# Arduino_Mega_Breakout_-_Schematic.net
KiCad netlist of a schematic drawn in EAGLE
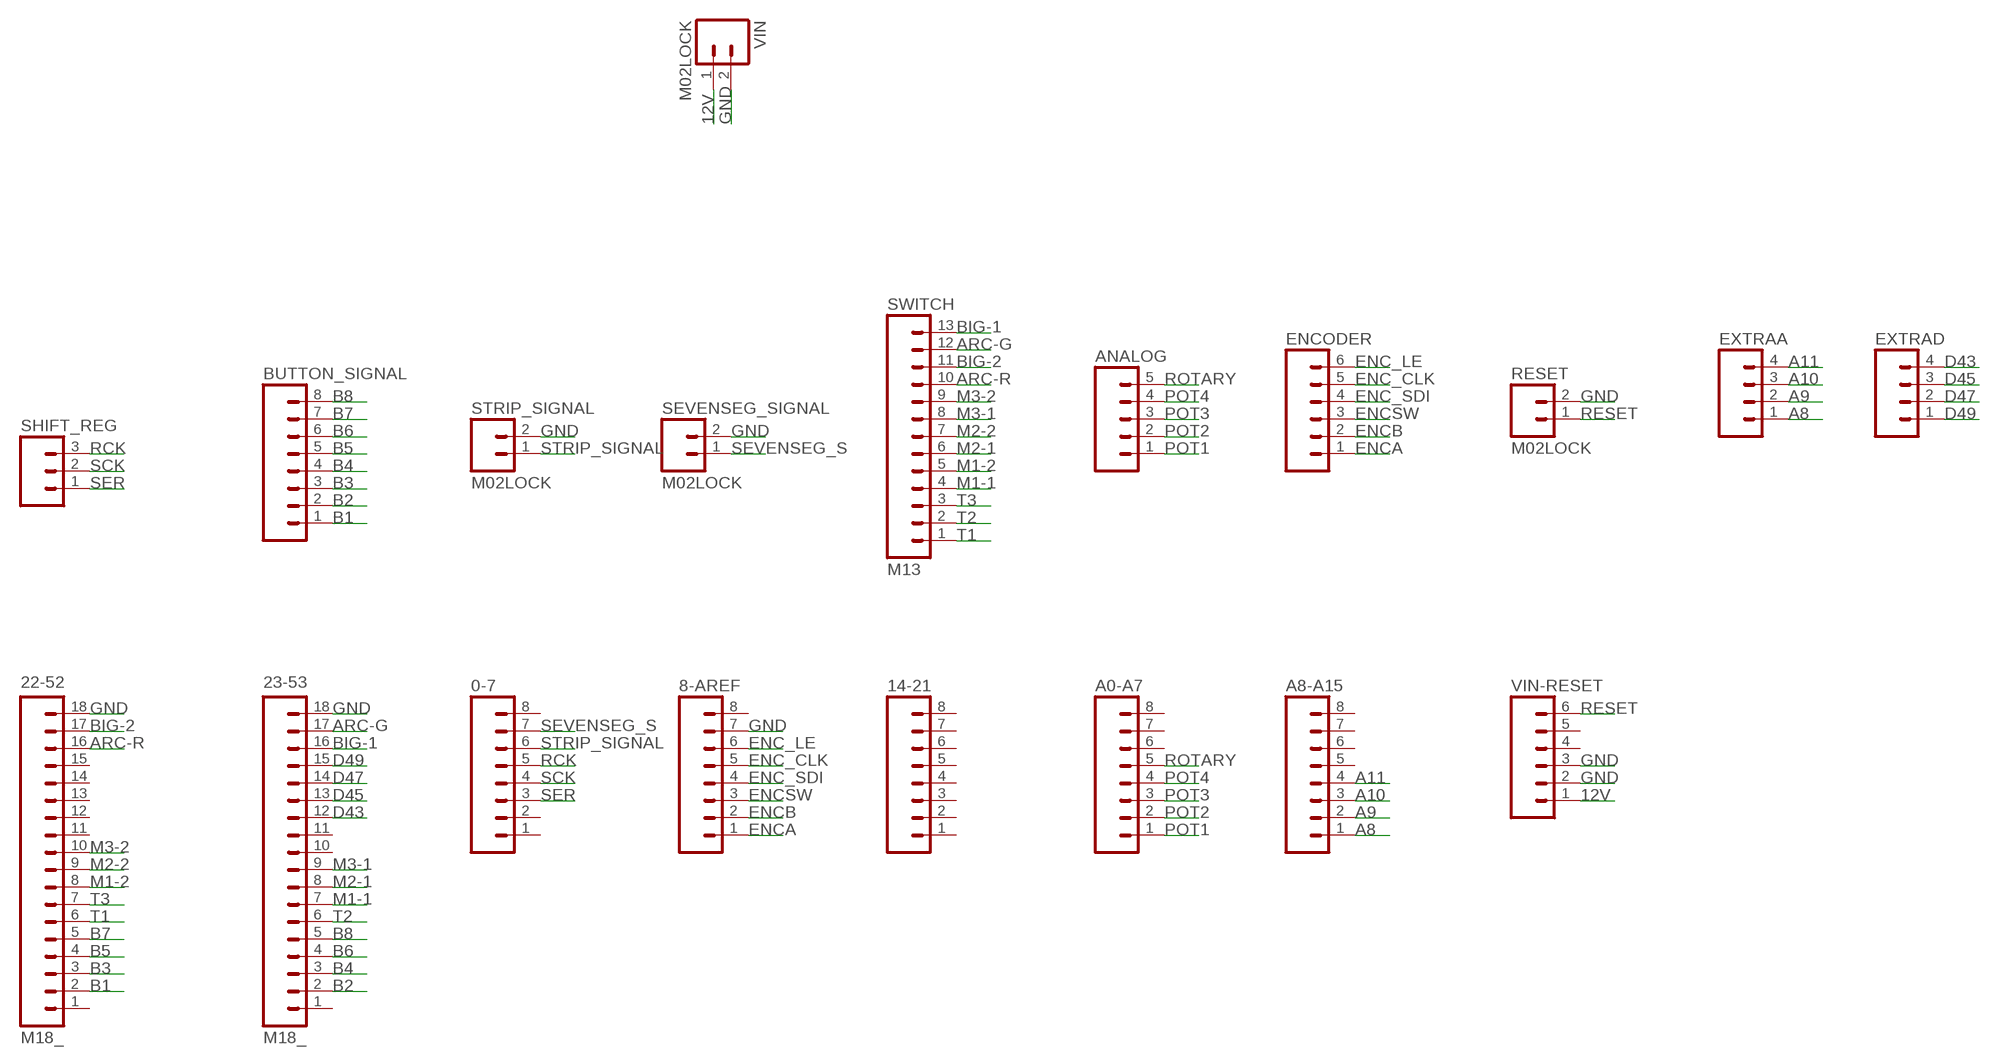
[diagram p0: schematic, sheet 1]

(export (version "E")
  (design (tool "Eeschema 10.0.6"))
  (components
    (comp (ref "0-7")
      (value "M08LOCK")
      (footprint "eagle-import:1X08_LOCK")
      (libsource (lib "eagle-import") (part "M08LOCK"))
    )
    (comp (ref "8-AREF")
      (value "M08LOCK")
      (footprint "eagle-import:1X08_LOCK")
      (libsource (lib "eagle-import") (part "M08LOCK"))
    )
    (comp (ref "14-21")
      (value "M08LOCK")
      (footprint "eagle-import:1X08_LOCK")
      (libsource (lib "eagle-import") (part "M08LOCK"))
    )
    (comp (ref "22-52")
      (value "M18_")
      (footprint "eagle-import:1X18")
      (libsource (lib "eagle-import") (part "M18_"))
    )
    (comp (ref "23-53")
      (value "M18_")
      (footprint "eagle-import:1X18")
      (libsource (lib "eagle-import") (part "M18_"))
    )
    (comp (ref "A0-A7")
      (value "M08LOCK")
      (footprint "eagle-import:1X08_LOCK")
      (libsource (lib "eagle-import") (part "M08LOCK"))
    )
    (comp (ref "A8-A15")
      (value "M08LOCK")
      (footprint "eagle-import:1X08_LOCK")
      (libsource (lib "eagle-import") (part "M08LOCK"))
    )
    (comp (ref "ANALOG")
      (value "M05LOCK")
      (footprint "eagle-import:1X05_LOCK")
      (libsource (lib "eagle-import") (part "M05LOCK"))
    )
    (comp (ref "BUTTON_SIGNAL")
      (value "M08")
      (footprint "eagle-import:1X08_PIN1_NO_SILK")
      (libsource (lib "eagle-import") (part "M08"))
    )
    (comp (ref "ENCODER")
      (value "M06LOCK")
      (footprint "eagle-import:1X06_LOCK")
      (libsource (lib "eagle-import") (part "M06LOCK"))
    )
    (comp (ref "EXTRAA")
      (value "M04LOCK")
      (footprint "eagle-import:1X04_LOCK")
      (libsource (lib "eagle-import") (part "M04LOCK"))
    )
    (comp (ref "EXTRAD")
      (value "M04PTH")
      (footprint "eagle-import:1X04")
      (libsource (lib "eagle-import") (part "M04PTH"))
    )
    (comp (ref "RESET")
      (value "M02LOCK")
      (footprint "eagle-import:1X02_LOCK")
      (libsource (lib "eagle-import") (part "M02LOCK"))
    )
    (comp (ref "SEVENSEG_SIGNAL")
      (value "M02LOCK")
      (footprint "eagle-import:1X02_LOCK")
      (libsource (lib "eagle-import") (part "M02LOCK"))
    )
    (comp (ref "SHIFT_REG")
      (value "M03LOCK")
      (footprint "eagle-import:1X03_LOCK")
      (libsource (lib "eagle-import") (part "M03LOCK"))
    )
    (comp (ref "STRIP_SIGNAL")
      (value "M02LOCK")
      (footprint "eagle-import:1X02_LOCK")
      (libsource (lib "eagle-import") (part "M02LOCK"))
    )
    (comp (ref "SWITCH")
      (value "M13")
      (footprint "eagle-import:1X13")
      (libsource (lib "eagle-import") (part "M13"))
    )
    (comp (ref "VIN")
      (value "M02LOCK")
      (footprint "eagle-import:1X02_LOCK")
      (libsource (lib "eagle-import") (part "M02LOCK"))
    )
    (comp (ref "VIN-RESET")
      (value "M06LOCK")
      (footprint "eagle-import:1X06_LOCK")
      (libsource (lib "eagle-import") (part "M06LOCK"))
    )
  )
  (nets
    (net (code "1") (name "/12V") (class "Default")
      (node (ref "VIN") (pin "1") (pinfunction "1_1") (pintype "passive"))
      (node (ref "VIN-RESET") (pin "1") (pinfunction "1_1") (pintype "passive"))
    )
    (net (code "2") (name "/A8") (class "Default")
      (node (ref "A8-A15") (pin "1") (pinfunction "1_1") (pintype "passive"))
      (node (ref "EXTRAA") (pin "1") (pinfunction "1_1") (pintype "passive"))
    )
    (net (code "3") (name "/A9") (class "Default")
      (node (ref "A8-A15") (pin "2") (pinfunction "2_2") (pintype "passive"))
      (node (ref "EXTRAA") (pin "2") (pinfunction "2_2") (pintype "passive"))
    )
    (net (code "4") (name "/A10") (class "Default")
      (node (ref "A8-A15") (pin "3") (pinfunction "3_3") (pintype "passive"))
      (node (ref "EXTRAA") (pin "3") (pinfunction "3_3") (pintype "passive"))
    )
    (net (code "5") (name "/A11") (class "Default")
      (node (ref "A8-A15") (pin "4") (pinfunction "4_4") (pintype "passive"))
      (node (ref "EXTRAA") (pin "4") (pinfunction "4_4") (pintype "passive"))
    )
    (net (code "6") (name "/ARC-G") (class "Default")
      (node (ref "23-53") (pin "17") (pinfunction "17_17") (pintype "passive"))
      (node (ref "SWITCH") (pin "12") (pinfunction "12_12") (pintype "passive"))
    )
    (net (code "7") (name "/ARC-R") (class "Default")
      (node (ref "22-52") (pin "16") (pinfunction "16_16") (pintype "passive"))
      (node (ref "SWITCH") (pin "10") (pinfunction "10_10") (pintype "passive"))
    )
    (net (code "8") (name "/B1") (class "Default")
      (node (ref "22-52") (pin "2") (pinfunction "2_2") (pintype "passive"))
      (node (ref "BUTTON_SIGNAL") (pin "1") (pinfunction "1_1") (pintype "passive"))
    )
    (net (code "9") (name "/B2") (class "Default")
      (node (ref "23-53") (pin "2") (pinfunction "2_2") (pintype "passive"))
      (node (ref "BUTTON_SIGNAL") (pin "2") (pinfunction "2_2") (pintype "passive"))
    )
    (net (code "10") (name "/B3") (class "Default")
      (node (ref "22-52") (pin "3") (pinfunction "3_3") (pintype "passive"))
      (node (ref "BUTTON_SIGNAL") (pin "3") (pinfunction "3_3") (pintype "passive"))
    )
    (net (code "11") (name "/B4") (class "Default")
      (node (ref "23-53") (pin "3") (pinfunction "3_3") (pintype "passive"))
      (node (ref "BUTTON_SIGNAL") (pin "4") (pinfunction "4_4") (pintype "passive"))
    )
    (net (code "12") (name "/B5") (class "Default")
      (node (ref "22-52") (pin "4") (pinfunction "4_4") (pintype "passive"))
      (node (ref "BUTTON_SIGNAL") (pin "5") (pinfunction "5_5") (pintype "passive"))
    )
    (net (code "13") (name "/B6") (class "Default")
      (node (ref "23-53") (pin "4") (pinfunction "4_4") (pintype "passive"))
      (node (ref "BUTTON_SIGNAL") (pin "6") (pinfunction "6_6") (pintype "passive"))
    )
    (net (code "14") (name "/B7") (class "Default")
      (node (ref "22-52") (pin "5") (pinfunction "5_5") (pintype "passive"))
      (node (ref "BUTTON_SIGNAL") (pin "7") (pinfunction "7_7") (pintype "passive"))
    )
    (net (code "15") (name "/B8") (class "Default")
      (node (ref "23-53") (pin "5") (pinfunction "5_5") (pintype "passive"))
      (node (ref "BUTTON_SIGNAL") (pin "8") (pinfunction "8_8") (pintype "passive"))
    )
    (net (code "16") (name "/BIG-1") (class "Default")
      (node (ref "23-53") (pin "16") (pinfunction "16_16") (pintype "passive"))
      (node (ref "SWITCH") (pin "13") (pinfunction "13_13") (pintype "passive"))
    )
    (net (code "17") (name "/BIG-2") (class "Default")
      (node (ref "22-52") (pin "17") (pinfunction "17_17") (pintype "passive"))
      (node (ref "SWITCH") (pin "11") (pinfunction "11_11") (pintype "passive"))
    )
    (net (code "18") (name "/D43") (class "Default")
      (node (ref "23-53") (pin "12") (pinfunction "12_12") (pintype "passive"))
      (node (ref "EXTRAD") (pin "4") (pinfunction "4_4") (pintype "passive"))
    )
    (net (code "19") (name "/D45") (class "Default")
      (node (ref "23-53") (pin "13") (pinfunction "13_13") (pintype "passive"))
      (node (ref "EXTRAD") (pin "3") (pinfunction "3_3") (pintype "passive"))
    )
    (net (code "20") (name "/D47") (class "Default")
      (node (ref "23-53") (pin "14") (pinfunction "14_14") (pintype "passive"))
      (node (ref "EXTRAD") (pin "2") (pinfunction "2_2") (pintype "passive"))
    )
    (net (code "21") (name "/D49") (class "Default")
      (node (ref "23-53") (pin "15") (pinfunction "15_15") (pintype "passive"))
      (node (ref "EXTRAD") (pin "1") (pinfunction "1_1") (pintype "passive"))
    )
    (net (code "22") (name "/ENCA") (class "Default")
      (node (ref "8-AREF") (pin "1") (pinfunction "1_1") (pintype "passive"))
      (node (ref "ENCODER") (pin "1") (pinfunction "1_1") (pintype "passive"))
    )
    (net (code "23") (name "/ENCB") (class "Default")
      (node (ref "8-AREF") (pin "2") (pinfunction "2_2") (pintype "passive"))
      (node (ref "ENCODER") (pin "2") (pinfunction "2_2") (pintype "passive"))
    )
    (net (code "24") (name "/ENCSW") (class "Default")
      (node (ref "8-AREF") (pin "3") (pinfunction "3_3") (pintype "passive"))
      (node (ref "ENCODER") (pin "3") (pinfunction "3_3") (pintype "passive"))
    )
    (net (code "25") (name "/ENC_CLK") (class "Default")
      (node (ref "8-AREF") (pin "5") (pinfunction "5_5") (pintype "passive"))
      (node (ref "ENCODER") (pin "5") (pinfunction "5_5") (pintype "passive"))
    )
    (net (code "26") (name "/ENC_LE") (class "Default")
      (node (ref "8-AREF") (pin "6") (pinfunction "6_6") (pintype "passive"))
      (node (ref "ENCODER") (pin "6") (pinfunction "6_6") (pintype "passive"))
    )
    (net (code "27") (name "/ENC_SDI") (class "Default")
      (node (ref "8-AREF") (pin "4") (pinfunction "4_4") (pintype "passive"))
      (node (ref "ENCODER") (pin "4") (pinfunction "4_4") (pintype "passive"))
    )
    (net (code "28") (name "/GND") (class "Default")
      (node (ref "22-52") (pin "18") (pinfunction "18_18") (pintype "passive"))
      (node (ref "23-53") (pin "18") (pinfunction "18_18") (pintype "passive"))
      (node (ref "8-AREF") (pin "7") (pinfunction "7_7") (pintype "passive"))
      (node (ref "RESET") (pin "2") (pinfunction "2_2") (pintype "passive"))
      (node (ref "SEVENSEG_SIGNAL") (pin "2") (pinfunction "2_2") (pintype "passive"))
      (node (ref "STRIP_SIGNAL") (pin "2") (pinfunction "2_2") (pintype "passive"))
      (node (ref "VIN") (pin "2") (pinfunction "2_2") (pintype "passive"))
      (node (ref "VIN-RESET") (pin "2") (pinfunction "2_2") (pintype "passive"))
      (node (ref "VIN-RESET") (pin "3") (pinfunction "3_3") (pintype "passive"))
    )
    (net (code "29") (name "/M1-1") (class "Default")
      (node (ref "23-53") (pin "7") (pinfunction "7_7") (pintype "passive"))
      (node (ref "SWITCH") (pin "4") (pinfunction "4_4") (pintype "passive"))
    )
    (net (code "30") (name "/M1-2") (class "Default")
      (node (ref "22-52") (pin "8") (pinfunction "8_8") (pintype "passive"))
      (node (ref "SWITCH") (pin "5") (pinfunction "5_5") (pintype "passive"))
    )
    (net (code "31") (name "/M2-1") (class "Default")
      (node (ref "23-53") (pin "8") (pinfunction "8_8") (pintype "passive"))
      (node (ref "SWITCH") (pin "6") (pinfunction "6_6") (pintype "passive"))
    )
    (net (code "32") (name "/M2-2") (class "Default")
      (node (ref "22-52") (pin "9") (pinfunction "9_9") (pintype "passive"))
      (node (ref "SWITCH") (pin "7") (pinfunction "7_7") (pintype "passive"))
    )
    (net (code "33") (name "/M3-1") (class "Default")
      (node (ref "23-53") (pin "9") (pinfunction "9_9") (pintype "passive"))
      (node (ref "SWITCH") (pin "8") (pinfunction "8_8") (pintype "passive"))
    )
    (net (code "34") (name "/M3-2") (class "Default")
      (node (ref "22-52") (pin "10") (pinfunction "10_10") (pintype "passive"))
      (node (ref "SWITCH") (pin "9") (pinfunction "9_9") (pintype "passive"))
    )
    (net (code "35") (name "/POT1") (class "Default")
      (node (ref "A0-A7") (pin "1") (pinfunction "1_1") (pintype "passive"))
      (node (ref "ANALOG") (pin "1") (pinfunction "1_1") (pintype "passive"))
    )
    (net (code "36") (name "/POT2") (class "Default")
      (node (ref "A0-A7") (pin "2") (pinfunction "2_2") (pintype "passive"))
      (node (ref "ANALOG") (pin "2") (pinfunction "2_2") (pintype "passive"))
    )
    (net (code "37") (name "/POT3") (class "Default")
      (node (ref "A0-A7") (pin "3") (pinfunction "3_3") (pintype "passive"))
      (node (ref "ANALOG") (pin "3") (pinfunction "3_3") (pintype "passive"))
    )
    (net (code "38") (name "/POT4") (class "Default")
      (node (ref "A0-A7") (pin "4") (pinfunction "4_4") (pintype "passive"))
      (node (ref "ANALOG") (pin "4") (pinfunction "4_4") (pintype "passive"))
    )
    (net (code "39") (name "/RCK") (class "Default")
      (node (ref "0-7") (pin "5") (pinfunction "5_5") (pintype "passive"))
      (node (ref "SHIFT_REG") (pin "3") (pinfunction "3_3") (pintype "passive"))
    )
    (net (code "40") (name "/RESET") (class "Default")
      (node (ref "RESET") (pin "1") (pinfunction "1_1") (pintype "passive"))
      (node (ref "VIN-RESET") (pin "6") (pinfunction "6_6") (pintype "passive"))
    )
    (net (code "41") (name "/ROTARY") (class "Default")
      (node (ref "A0-A7") (pin "5") (pinfunction "5_5") (pintype "passive"))
      (node (ref "ANALOG") (pin "5") (pinfunction "5_5") (pintype "passive"))
    )
    (net (code "42") (name "/SCK") (class "Default")
      (node (ref "0-7") (pin "4") (pinfunction "4_4") (pintype "passive"))
      (node (ref "SHIFT_REG") (pin "2") (pinfunction "2_2") (pintype "passive"))
    )
    (net (code "43") (name "/SER") (class "Default")
      (node (ref "0-7") (pin "3") (pinfunction "3_3") (pintype "passive"))
      (node (ref "SHIFT_REG") (pin "1") (pinfunction "1_1") (pintype "passive"))
    )
    (net (code "44") (name "/SEVENSEG_S") (class "Default")
      (node (ref "0-7") (pin "7") (pinfunction "7_7") (pintype "passive"))
      (node (ref "SEVENSEG_SIGNAL") (pin "1") (pinfunction "1_1") (pintype "passive"))
    )
    (net (code "45") (name "/STRIP_SIGNAL") (class "Default")
      (node (ref "0-7") (pin "6") (pinfunction "6_6") (pintype "passive"))
      (node (ref "STRIP_SIGNAL") (pin "1") (pinfunction "1_1") (pintype "passive"))
    )
    (net (code "46") (name "/T1") (class "Default")
      (node (ref "22-52") (pin "6") (pinfunction "6_6") (pintype "passive"))
      (node (ref "SWITCH") (pin "1") (pinfunction "1_1") (pintype "passive"))
    )
    (net (code "47") (name "/T2") (class "Default")
      (node (ref "23-53") (pin "6") (pinfunction "6_6") (pintype "passive"))
      (node (ref "SWITCH") (pin "2") (pinfunction "2_2") (pintype "passive"))
    )
    (net (code "48") (name "/T3") (class "Default")
      (node (ref "22-52") (pin "7") (pinfunction "7_7") (pintype "passive"))
      (node (ref "SWITCH") (pin "3") (pinfunction "3_3") (pintype "passive"))
    )
    (net (code "49") (name "unconnected-(0-7-Pad1)") (class "Default")
      (node (ref "0-7") (pin "1") (pinfunction "1_1") (pintype "passive"))
    )
    (net (code "50") (name "unconnected-(0-7-Pad2)") (class "Default")
      (node (ref "0-7") (pin "2") (pinfunction "2_2") (pintype "passive"))
    )
    (net (code "51") (name "unconnected-(0-7-Pad8)") (class "Default")
      (node (ref "0-7") (pin "8") (pinfunction "8_8") (pintype "passive"))
    )
    (net (code "52") (name "unconnected-(8-AREF-Pad8)") (class "Default")
      (node (ref "8-AREF") (pin "8") (pinfunction "8_8") (pintype "passive"))
    )
    (net (code "53") (name "unconnected-(14-21-Pad1)") (class "Default")
      (node (ref "14-21") (pin "1") (pinfunction "1_1") (pintype "passive"))
    )
    (net (code "54") (name "unconnected-(14-21-Pad2)") (class "Default")
      (node (ref "14-21") (pin "2") (pinfunction "2_2") (pintype "passive"))
    )
    (net (code "55") (name "unconnected-(14-21-Pad3)") (class "Default")
      (node (ref "14-21") (pin "3") (pinfunction "3_3") (pintype "passive"))
    )
    (net (code "56") (name "unconnected-(14-21-Pad4)") (class "Default")
      (node (ref "14-21") (pin "4") (pinfunction "4_4") (pintype "passive"))
    )
    (net (code "57") (name "unconnected-(14-21-Pad5)") (class "Default")
      (node (ref "14-21") (pin "5") (pinfunction "5_5") (pintype "passive"))
    )
    (net (code "58") (name "unconnected-(14-21-Pad6)") (class "Default")
      (node (ref "14-21") (pin "6") (pinfunction "6_6") (pintype "passive"))
    )
    (net (code "59") (name "unconnected-(14-21-Pad7)") (class "Default")
      (node (ref "14-21") (pin "7") (pinfunction "7_7") (pintype "passive"))
    )
    (net (code "60") (name "unconnected-(14-21-Pad8)") (class "Default")
      (node (ref "14-21") (pin "8") (pinfunction "8_8") (pintype "passive"))
    )
    (net (code "61") (name "unconnected-(22-52-Pad1)") (class "Default")
      (node (ref "22-52") (pin "1") (pinfunction "1_1") (pintype "passive"))
    )
    (net (code "62") (name "unconnected-(22-52-Pad11)") (class "Default")
      (node (ref "22-52") (pin "11") (pinfunction "11_11") (pintype "passive"))
    )
    (net (code "63") (name "unconnected-(22-52-Pad12)") (class "Default")
      (node (ref "22-52") (pin "12") (pinfunction "12_12") (pintype "passive"))
    )
    (net (code "64") (name "unconnected-(22-52-Pad13)") (class "Default")
      (node (ref "22-52") (pin "13") (pinfunction "13_13") (pintype "passive"))
    )
    (net (code "65") (name "unconnected-(22-52-Pad14)") (class "Default")
      (node (ref "22-52") (pin "14") (pinfunction "14_14") (pintype "passive"))
    )
    (net (code "66") (name "unconnected-(22-52-Pad15)") (class "Default")
      (node (ref "22-52") (pin "15") (pinfunction "15_15") (pintype "passive"))
    )
    (net (code "67") (name "unconnected-(23-53-Pad1)") (class "Default")
      (node (ref "23-53") (pin "1") (pinfunction "1_1") (pintype "passive"))
    )
    (net (code "68") (name "unconnected-(23-53-Pad10)") (class "Default")
      (node (ref "23-53") (pin "10") (pinfunction "10_10") (pintype "passive"))
    )
    (net (code "69") (name "unconnected-(23-53-Pad11)") (class "Default")
      (node (ref "23-53") (pin "11") (pinfunction "11_11") (pintype "passive"))
    )
    (net (code "70") (name "unconnected-(A0-A7-Pad6)") (class "Default")
      (node (ref "A0-A7") (pin "6") (pinfunction "6_6") (pintype "passive"))
    )
    (net (code "71") (name "unconnected-(A0-A7-Pad7)") (class "Default")
      (node (ref "A0-A7") (pin "7") (pinfunction "7_7") (pintype "passive"))
    )
    (net (code "72") (name "unconnected-(A0-A7-Pad8)") (class "Default")
      (node (ref "A0-A7") (pin "8") (pinfunction "8_8") (pintype "passive"))
    )
    (net (code "73") (name "unconnected-(A8-A15-Pad5)") (class "Default")
      (node (ref "A8-A15") (pin "5") (pinfunction "5_5") (pintype "passive"))
    )
    (net (code "74") (name "unconnected-(A8-A15-Pad6)") (class "Default")
      (node (ref "A8-A15") (pin "6") (pinfunction "6_6") (pintype "passive"))
    )
    (net (code "75") (name "unconnected-(A8-A15-Pad7)") (class "Default")
      (node (ref "A8-A15") (pin "7") (pinfunction "7_7") (pintype "passive"))
    )
    (net (code "76") (name "unconnected-(A8-A15-Pad8)") (class "Default")
      (node (ref "A8-A15") (pin "8") (pinfunction "8_8") (pintype "passive"))
    )
    (net (code "77") (name "unconnected-(VIN-RESET-Pad4)") (class "Default")
      (node (ref "VIN-RESET") (pin "4") (pinfunction "4_4") (pintype "passive"))
    )
    (net (code "78") (name "unconnected-(VIN-RESET-Pad5)") (class "Default")
      (node (ref "VIN-RESET") (pin "5") (pinfunction "5_5") (pintype "passive"))
    )
  )
)
